# Elecctronic_Dice.net
KiCad netlist of a schematic drawn in EAGLE
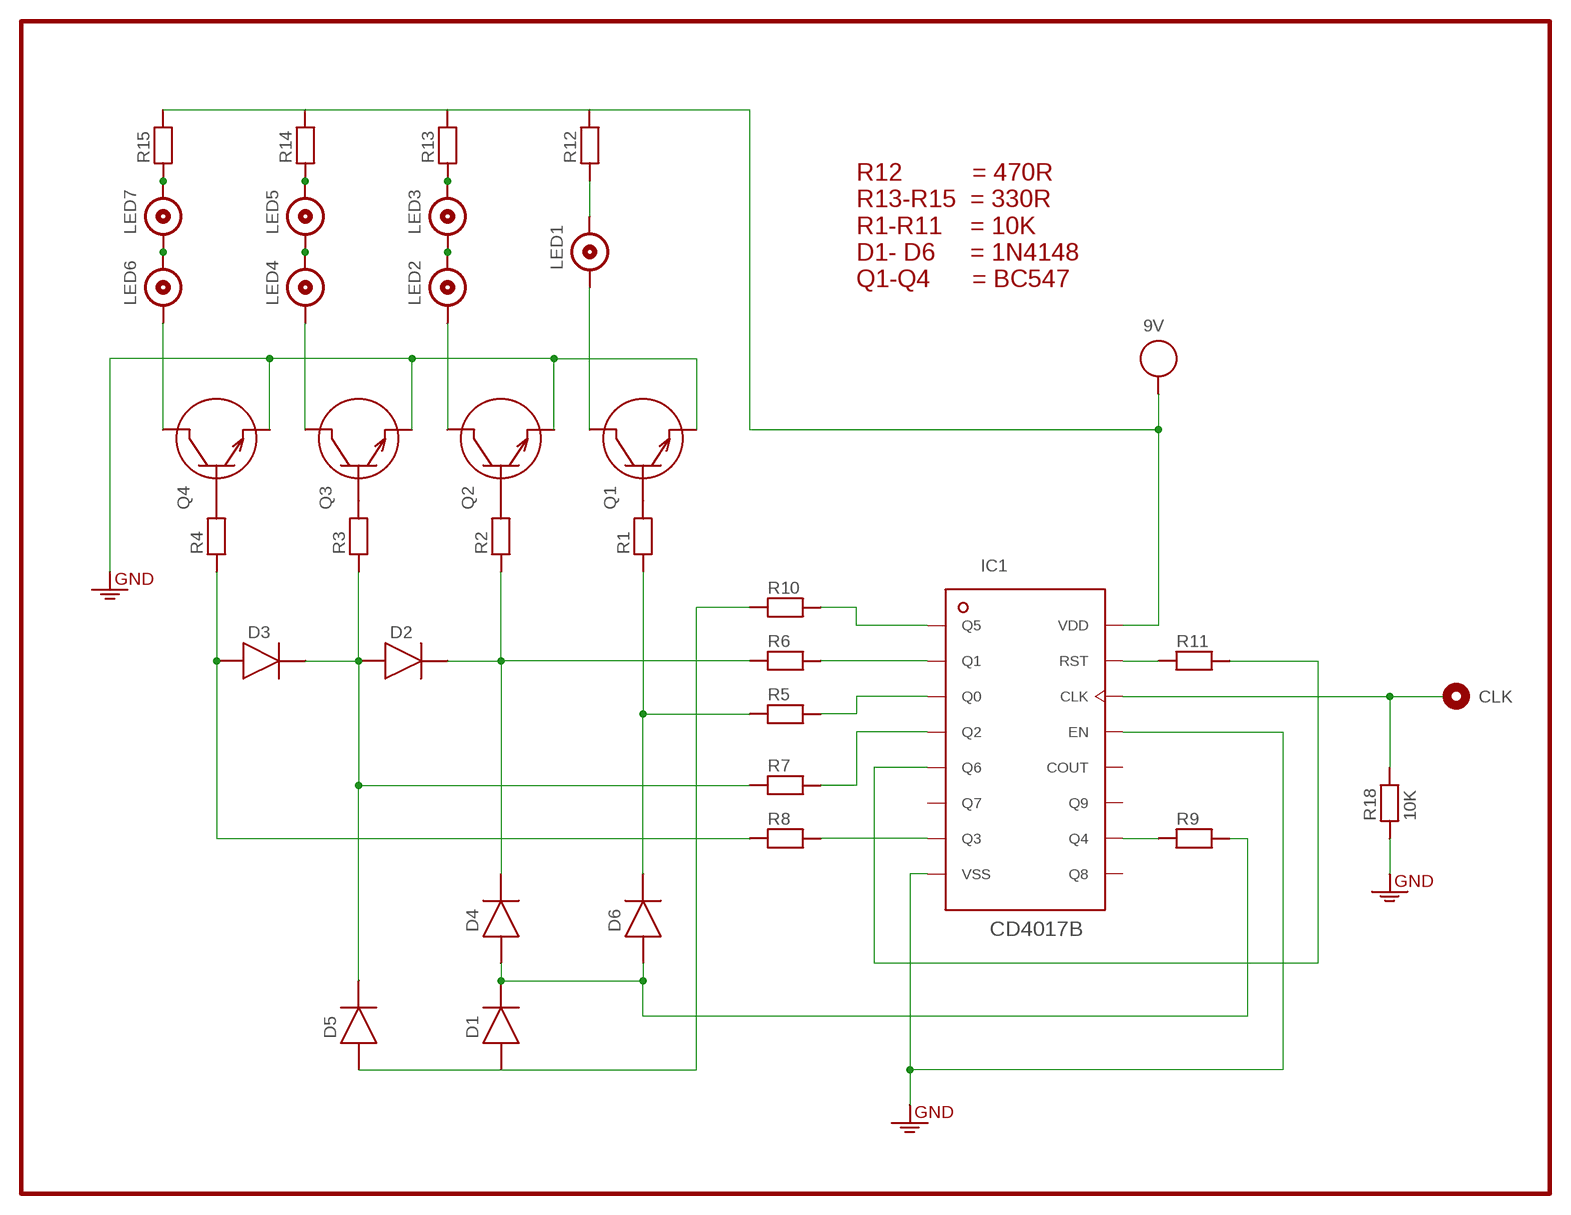
[diagram p0: schematic, sheet 1]
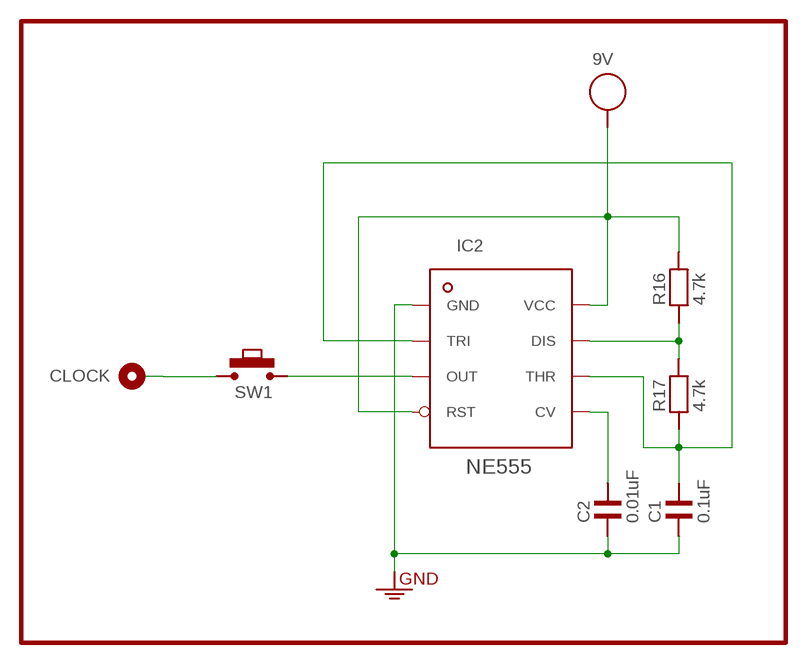
[diagram p1: schematic, sheet 2]

(export (version "E")
  (design (tool "Eeschema 10.0.6"))
  (components
    (comp (ref "CLK")
      (value "POINT")
      (footprint "eagle-import:1POINT")
      (libsource (lib "eagle-import") (part "POINT"))
    )
    (comp (ref "D1")
      (value "DIODE_NORMAL")
      (footprint "eagle-import:DIO_3G")
      (libsource (lib "eagle-import") (part "DIODE_NORMAL"))
    )
    (comp (ref "D2")
      (value "DIODE_NORMAL")
      (footprint "eagle-import:DIO_3G")
      (libsource (lib "eagle-import") (part "DIODE_NORMAL"))
    )
    (comp (ref "D3")
      (value "DIODE_NORMAL")
      (footprint "eagle-import:DIO_3G")
      (libsource (lib "eagle-import") (part "DIODE_NORMAL"))
    )
    (comp (ref "D4")
      (value "DIODE_NORMAL")
      (footprint "eagle-import:DIO_3G")
      (libsource (lib "eagle-import") (part "DIODE_NORMAL"))
    )
    (comp (ref "D5")
      (value "DIODE_NORMAL")
      (footprint "eagle-import:DIO_3G")
      (libsource (lib "eagle-import") (part "DIODE_NORMAL"))
    )
    (comp (ref "D6")
      (value "DIODE_NORMAL")
      (footprint "eagle-import:DIO_3G")
      (libsource (lib "eagle-import") (part "DIODE_NORMAL"))
    )
    (comp (ref "IC1")
      (value "CD4017B")
      (footprint "eagle-import:16PIN_IC")
      (libsource (lib "eagle-import") (part "CD4017B"))
    )
    (comp (ref "LED1")
      (value "LED")
      (footprint "eagle-import:LED_OG")
      (libsource (lib "eagle-import") (part "LED"))
    )
    (comp (ref "LED2")
      (value "LED")
      (footprint "eagle-import:LED_OG")
      (libsource (lib "eagle-import") (part "LED"))
    )
    (comp (ref "LED3")
      (value "LED")
      (footprint "eagle-import:LED_OG")
      (libsource (lib "eagle-import") (part "LED"))
    )
    (comp (ref "LED4")
      (value "LED")
      (footprint "eagle-import:LED_OG")
      (libsource (lib "eagle-import") (part "LED"))
    )
    (comp (ref "LED5")
      (value "LED")
      (footprint "eagle-import:LED_OG")
      (libsource (lib "eagle-import") (part "LED"))
    )
    (comp (ref "LED6")
      (value "LED")
      (footprint "eagle-import:LED_OG")
      (libsource (lib "eagle-import") (part "LED"))
    )
    (comp (ref "LED7")
      (value "LED")
      (footprint "eagle-import:LED_OG")
      (libsource (lib "eagle-import") (part "LED"))
    )
    (comp (ref "Q1")
      (value "TRANSISTOR_NPN")
      (footprint "eagle-import:TRANSISTOR")
      (libsource (lib "eagle-import") (part "TRANSISTOR_NPN"))
    )
    (comp (ref "Q2")
      (value "TRANSISTOR_NPN")
      (footprint "eagle-import:TRANSISTOR")
      (libsource (lib "eagle-import") (part "TRANSISTOR_NPN"))
    )
    (comp (ref "Q3")
      (value "TRANSISTOR_NPN")
      (footprint "eagle-import:TRANSISTOR")
      (libsource (lib "eagle-import") (part "TRANSISTOR_NPN"))
    )
    (comp (ref "Q4")
      (value "TRANSISTOR_NPN")
      (footprint "eagle-import:TRANSISTOR")
      (libsource (lib "eagle-import") (part "TRANSISTOR_NPN"))
    )
    (comp (ref "R1")
      (value "RESISTOR_NORMAL")
      (footprint "eagle-import:RES_3G")
      (libsource (lib "eagle-import") (part "RESISTOR_NORMAL"))
    )
    (comp (ref "R2")
      (value "RESISTOR_NORMAL")
      (footprint "eagle-import:RES_3G")
      (libsource (lib "eagle-import") (part "RESISTOR_NORMAL"))
    )
    (comp (ref "R3")
      (value "RESISTOR_NORMAL")
      (footprint "eagle-import:RES_3G")
      (libsource (lib "eagle-import") (part "RESISTOR_NORMAL"))
    )
    (comp (ref "R4")
      (value "RESISTOR_NORMAL")
      (footprint "eagle-import:RES_3G")
      (libsource (lib "eagle-import") (part "RESISTOR_NORMAL"))
    )
    (comp (ref "R5")
      (value "RESISTOR_NORMAL")
      (footprint "eagle-import:RES_3G")
      (libsource (lib "eagle-import") (part "RESISTOR_NORMAL"))
    )
    (comp (ref "R6")
      (value "RESISTOR_NORMAL")
      (footprint "eagle-import:RES_3G")
      (libsource (lib "eagle-import") (part "RESISTOR_NORMAL"))
    )
    (comp (ref "R7")
      (value "RESISTOR_NORMAL")
      (footprint "eagle-import:RES_3G")
      (libsource (lib "eagle-import") (part "RESISTOR_NORMAL"))
    )
    (comp (ref "R8")
      (value "RESISTOR_NORMAL")
      (footprint "eagle-import:RES_3G")
      (libsource (lib "eagle-import") (part "RESISTOR_NORMAL"))
    )
    (comp (ref "R9")
      (value "RESISTOR_NORMAL")
      (footprint "eagle-import:RES_3G")
      (libsource (lib "eagle-import") (part "RESISTOR_NORMAL"))
    )
    (comp (ref "R10")
      (value "RESISTOR_NORMAL")
      (footprint "eagle-import:RES_3G")
      (libsource (lib "eagle-import") (part "RESISTOR_NORMAL"))
    )
    (comp (ref "R11")
      (value "RESISTOR_NORMAL")
      (footprint "eagle-import:RES_3G")
      (libsource (lib "eagle-import") (part "RESISTOR_NORMAL"))
    )
    (comp (ref "R12")
      (value "RESISTOR_NORMAL")
      (footprint "eagle-import:RES_3G")
      (libsource (lib "eagle-import") (part "RESISTOR_NORMAL"))
    )
    (comp (ref "R13")
      (value "RESISTOR_NORMAL")
      (footprint "eagle-import:RES_3G")
      (libsource (lib "eagle-import") (part "RESISTOR_NORMAL"))
    )
    (comp (ref "R14")
      (value "RESISTOR_NORMAL")
      (footprint "eagle-import:RES_3G")
      (libsource (lib "eagle-import") (part "RESISTOR_NORMAL"))
    )
    (comp (ref "R15")
      (value "RESISTOR_NORMAL")
      (footprint "eagle-import:RES_3G")
      (libsource (lib "eagle-import") (part "RESISTOR_NORMAL"))
    )
    (comp (ref "R18")
      (value "10K")
      (footprint "eagle-import:RES_3G")
      (libsource (lib "eagle-import") (part "RESISTOR_NORMAL"))
    )
    (comp (ref "U$1")
      (value "GND")
      (footprint "eagle-import:1POINT")
      (libsource (lib "eagle-import") (part "SAM Labs Components_GND"))
    )
    (comp (ref "U$2")
      (value "GND")
      (footprint "eagle-import:1POINT")
      (libsource (lib "eagle-import") (part "SAM Labs Components_GND"))
    )
    (comp (ref "U$3")
      (value "9V")
      (footprint "eagle-import:1POINT")
      (libsource (lib "eagle-import") (part "SAM Labs Components_VCC"))
    )
    (comp (ref "U$5")
      (value "GND")
      (footprint "eagle-import:1POINT")
      (libsource (lib "eagle-import") (part "SAM Labs Components_GND"))
    )
    (comp (ref "9V")
      (value "9V")
      (footprint "eagle-import:1POINT")
      (libsource (lib "eagle-import") (part "VCC"))
    )
    (comp (ref "C1")
      (value "0.1uF")
      (footprint "eagle-import:2POINT")
      (libsource (lib "eagle-import") (part "CAP_NPOL"))
    )
    (comp (ref "C2")
      (value "0.01uF")
      (footprint "eagle-import:2POINT")
      (libsource (lib "eagle-import") (part "CAP_NPOL"))
    )
    (comp (ref "CLOCK")
      (value "POINT")
      (footprint "eagle-import:1POINT")
      (libsource (lib "eagle-import") (part "POINT"))
    )
    (comp (ref "IC2")
      (value "NE555")
      (footprint "eagle-import:8PIN_IC")
      (libsource (lib "eagle-import") (part "NE555"))
    )
    (comp (ref "R16")
      (value "4.7k")
      (footprint "eagle-import:RES_3G")
      (libsource (lib "eagle-import") (part "RESISTOR_NORMAL"))
    )
    (comp (ref "R17")
      (value "4.7k")
      (footprint "eagle-import:RES_3G")
      (libsource (lib "eagle-import") (part "RESISTOR_NORMAL"))
    )
    (comp (ref "SW1")
      (value "PUSHSWITCH")
      (footprint "eagle-import:PUSHSWITCH")
      (libsource (lib "eagle-import") (part "PUSHSWITCH"))
    )
    (comp (ref "U$4")
      (value "GND")
      (footprint "eagle-import:1POINT")
      (libsource (lib "eagle-import") (part "GND"))
    )
  )
  (nets
    (net (code "1") (name "Net-(CLOCK-PadP$1)") (class "Default")
      (node (ref "CLOCK") (pin "P$1") (pinfunction "P$1_P$1") (pintype "power_in"))
      (node (ref "SW1") (pin "P$1") (pinfunction "P$1_P$1") (pintype "bidirectional"))
      (node (ref "SW1") (pin "P$2") (pinfunction "P$1_P$2") (pintype "bidirectional"))
    )
    (net (code "2") (name "Net-(IC1-CLK)") (class "Default")
      (node (ref "CLK") (pin "P$1") (pinfunction "P$1_P$1") (pintype "power_in"))
      (node (ref "IC1") (pin "P$14") (pinfunction "CLK_P$14") (pintype "bidirectional"))
      (node (ref "R18") (pin "P$5") (pinfunction "P$2_P$5") (pintype "bidirectional"))
    )
    (net (code "3") (name "Net-(IC1-EN)") (class "Default")
      (node (ref "IC1") (pin "P$13") (pinfunction "EN_P$13") (pintype "bidirectional"))
      (node (ref "IC1") (pin "P$8") (pinfunction "VSS_P$8") (pintype "power_in"))
      (node (ref "U$2") (pin "P$1") (pinfunction "P$1_P$1") (pintype "bidirectional"))
    )
    (net (code "4") (name "Net-(IC1-Q0)") (class "Default")
      (node (ref "IC1") (pin "P$3") (pinfunction "Q0_P$3") (pintype "bidirectional"))
      (node (ref "R5") (pin "P$5") (pinfunction "P$2_P$5") (pintype "bidirectional"))
    )
    (net (code "5") (name "Net-(IC1-Q1)") (class "Default")
      (node (ref "IC1") (pin "P$2") (pinfunction "Q1_P$2") (pintype "bidirectional"))
      (node (ref "R6") (pin "P$5") (pinfunction "P$2_P$5") (pintype "bidirectional"))
    )
    (net (code "6") (name "Net-(IC1-Q2)") (class "Default")
      (node (ref "IC1") (pin "P$4") (pinfunction "Q2_P$4") (pintype "bidirectional"))
      (node (ref "R7") (pin "P$5") (pinfunction "P$2_P$5") (pintype "bidirectional"))
    )
    (net (code "7") (name "Net-(IC1-Q3)") (class "Default")
      (node (ref "IC1") (pin "P$7") (pinfunction "Q3_P$7") (pintype "bidirectional"))
      (node (ref "R8") (pin "P$5") (pinfunction "P$2_P$5") (pintype "bidirectional"))
    )
    (net (code "8") (name "Net-(IC1-Q4)") (class "Default")
      (node (ref "IC1") (pin "P$10") (pinfunction "Q4_P$10") (pintype "bidirectional"))
      (node (ref "R9") (pin "P$3") (pinfunction "P$1_P$3") (pintype "bidirectional"))
    )
    (net (code "9") (name "Net-(IC1-Q5)") (class "Default")
      (node (ref "IC1") (pin "P$1") (pinfunction "Q5_P$1") (pintype "bidirectional"))
      (node (ref "R10") (pin "P$5") (pinfunction "P$2_P$5") (pintype "bidirectional"))
    )
    (net (code "10") (name "Net-(IC1-Q6)") (class "Default")
      (node (ref "IC1") (pin "P$5") (pinfunction "Q6_P$5") (pintype "bidirectional"))
      (node (ref "R11") (pin "P$5") (pinfunction "P$2_P$5") (pintype "bidirectional"))
    )
    (net (code "11") (name "Net-(IC1-RST)") (class "Default")
      (node (ref "IC1") (pin "P$15") (pinfunction "RST_P$15") (pintype "bidirectional"))
      (node (ref "R11") (pin "P$3") (pinfunction "P$1_P$3") (pintype "bidirectional"))
    )
    (net (code "12") (name "Net-(IC1-VDD)") (class "Default")
      (node (ref "IC1") (pin "P$16") (pinfunction "VDD_P$16") (pintype "power_in"))
      (node (ref "R12") (pin "P$5") (pinfunction "P$2_P$5") (pintype "bidirectional"))
      (node (ref "R15") (pin "P$5") (pinfunction "P$2_P$5") (pintype "bidirectional"))
      (node (ref "U$3") (pin "P$1") (pinfunction "P$1_P$1") (pintype "bidirectional"))
    )
    (net (code "13") (name "Net-(IC2-CV)") (class "Default")
      (node (ref "C2") (pin "P$2") (pinfunction "P$2_P$2") (pintype "bidirectional"))
      (node (ref "IC2") (pin "P$5") (pinfunction "CV_P$5") (pintype "bidirectional"))
    )
    (net (code "14") (name "Net-(IC2-DIS)") (class "Default")
      (node (ref "IC2") (pin "P$7") (pinfunction "DIS_P$7") (pintype "bidirectional"))
      (node (ref "R16") (pin "P$3") (pinfunction "P$1_P$3") (pintype "bidirectional"))
      (node (ref "R17") (pin "P$5") (pinfunction "P$2_P$5") (pintype "bidirectional"))
    )
    (net (code "15") (name "Net-(IC2-GND)") (class "Default")
      (node (ref "C1") (pin "P$1") (pinfunction "P$1_P$1") (pintype "bidirectional"))
      (node (ref "C2") (pin "P$1") (pinfunction "P$1_P$1") (pintype "bidirectional"))
      (node (ref "IC2") (pin "P$1") (pinfunction "GND_P$1") (pintype "power_in"))
      (node (ref "U$4") (pin "P$1") (pinfunction "P$1_P$1") (pintype "power_in"))
    )
    (net (code "16") (name "Net-(IC2-OUT)") (class "Default")
      (node (ref "IC2") (pin "P$3") (pinfunction "OUT_P$3") (pintype "bidirectional"))
      (node (ref "SW1") (pin "P$3") (pinfunction "P$2_P$3") (pintype "bidirectional"))
      (node (ref "SW1") (pin "P$4") (pinfunction "P$2_P$4") (pintype "bidirectional"))
    )
    (net (code "17") (name "Net-(IC2-RST)") (class "Default")
      (node (ref "9V") (pin "P$1") (pinfunction "P$1_P$1") (pintype "power_in"))
      (node (ref "IC2") (pin "P$4") (pinfunction "RST_P$4") (pintype "bidirectional"))
      (node (ref "IC2") (pin "P$8") (pinfunction "VCC_P$8") (pintype "power_in"))
      (node (ref "R16") (pin "P$5") (pinfunction "P$2_P$5") (pintype "bidirectional"))
    )
    (net (code "18") (name "Net-(IC2-THR)") (class "Default")
      (node (ref "C1") (pin "P$2") (pinfunction "P$2_P$2") (pintype "bidirectional"))
      (node (ref "IC2") (pin "P$2") (pinfunction "TRI_P$2") (pintype "bidirectional"))
      (node (ref "IC2") (pin "P$6") (pinfunction "THR_P$6") (pintype "bidirectional"))
      (node (ref "R17") (pin "P$3") (pinfunction "P$1_P$3") (pintype "bidirectional"))
    )
    (net (code "19") (name "Net-(LED1-PadP$2)") (class "Default")
      (node (ref "LED1") (pin "P$2") (pinfunction "P$2_P$2") (pintype "bidirectional"))
      (node (ref "Q1") (pin "P$3") (pinfunction "P$3_P$3") (pintype "bidirectional"))
    )
    (net (code "20") (name "Net-(LED2-PadP$1)") (class "Default")
      (node (ref "LED2") (pin "P$1") (pinfunction "P$1_P$1") (pintype "bidirectional"))
      (node (ref "LED3") (pin "P$2") (pinfunction "P$2_P$2") (pintype "bidirectional"))
    )
    (net (code "21") (name "Net-(LED2-PadP$2)") (class "Default")
      (node (ref "LED2") (pin "P$2") (pinfunction "P$2_P$2") (pintype "bidirectional"))
      (node (ref "Q2") (pin "P$3") (pinfunction "P$3_P$3") (pintype "bidirectional"))
    )
    (net (code "22") (name "Net-(LED4-PadP$1)") (class "Default")
      (node (ref "LED4") (pin "P$1") (pinfunction "P$1_P$1") (pintype "bidirectional"))
      (node (ref "LED5") (pin "P$2") (pinfunction "P$2_P$2") (pintype "bidirectional"))
    )
    (net (code "23") (name "Net-(LED4-PadP$2)") (class "Default")
      (node (ref "LED4") (pin "P$2") (pinfunction "P$2_P$2") (pintype "bidirectional"))
      (node (ref "Q3") (pin "P$3") (pinfunction "P$3_P$3") (pintype "bidirectional"))
    )
    (net (code "24") (name "Net-(LED6-PadP$1)") (class "Default")
      (node (ref "LED6") (pin "P$1") (pinfunction "P$1_P$1") (pintype "bidirectional"))
      (node (ref "LED7") (pin "P$2") (pinfunction "P$2_P$2") (pintype "bidirectional"))
    )
    (net (code "25") (name "Net-(LED6-PadP$2)") (class "Default")
      (node (ref "LED6") (pin "P$2") (pinfunction "P$2_P$2") (pintype "bidirectional"))
      (node (ref "Q4") (pin "P$3") (pinfunction "P$3_P$3") (pintype "bidirectional"))
    )
    (net (code "26") (name "Net-(Q1-PadP$1)") (class "Default")
      (node (ref "Q1") (pin "P$1") (pinfunction "P$1_P$1") (pintype "bidirectional"))
      (node (ref "Q2") (pin "P$1") (pinfunction "P$1_P$1") (pintype "bidirectional"))
      (node (ref "Q3") (pin "P$1") (pinfunction "P$1_P$1") (pintype "bidirectional"))
      (node (ref "Q4") (pin "P$1") (pinfunction "P$1_P$1") (pintype "bidirectional"))
      (node (ref "U$1") (pin "P$1") (pinfunction "P$1_P$1") (pintype "bidirectional"))
    )
    (net (code "27") (name "Net-(R1-P$1)") (class "Default")
      (node (ref "D6") (pin "N") (pinfunction "N_N") (pintype "bidirectional"))
      (node (ref "R1") (pin "P$3") (pinfunction "P$1_P$3") (pintype "bidirectional"))
      (node (ref "R5") (pin "P$3") (pinfunction "P$1_P$3") (pintype "bidirectional"))
    )
    (net (code "28") (name "Net-(R1-P$2)") (class "Default")
      (node (ref "Q1") (pin "P$2") (pinfunction "P$2_P$2") (pintype "bidirectional"))
      (node (ref "R1") (pin "P$5") (pinfunction "P$2_P$5") (pintype "bidirectional"))
    )
    (net (code "29") (name "Net-(R2-P$1)") (class "Default")
      (node (ref "D2") (pin "N") (pinfunction "N_N") (pintype "bidirectional"))
      (node (ref "D4") (pin "N") (pinfunction "N_N") (pintype "bidirectional"))
      (node (ref "R2") (pin "P$3") (pinfunction "P$1_P$3") (pintype "bidirectional"))
      (node (ref "R6") (pin "P$3") (pinfunction "P$1_P$3") (pintype "bidirectional"))
    )
    (net (code "30") (name "Net-(R2-P$2)") (class "Default")
      (node (ref "Q2") (pin "P$2") (pinfunction "P$2_P$2") (pintype "bidirectional"))
      (node (ref "R2") (pin "P$5") (pinfunction "P$2_P$5") (pintype "bidirectional"))
    )
    (net (code "31") (name "Net-(R3-P$1)") (class "Default")
      (node (ref "D2") (pin "P") (pinfunction "P_P") (pintype "bidirectional"))
      (node (ref "D3") (pin "N") (pinfunction "N_N") (pintype "bidirectional"))
      (node (ref "D5") (pin "N") (pinfunction "N_N") (pintype "bidirectional"))
      (node (ref "R3") (pin "P$3") (pinfunction "P$1_P$3") (pintype "bidirectional"))
      (node (ref "R7") (pin "P$3") (pinfunction "P$1_P$3") (pintype "bidirectional"))
    )
    (net (code "32") (name "Net-(R3-P$2)") (class "Default")
      (node (ref "Q3") (pin "P$2") (pinfunction "P$2_P$2") (pintype "bidirectional"))
      (node (ref "R3") (pin "P$5") (pinfunction "P$2_P$5") (pintype "bidirectional"))
    )
    (net (code "33") (name "Net-(R4-P$1)") (class "Default")
      (node (ref "D3") (pin "P") (pinfunction "P_P") (pintype "bidirectional"))
      (node (ref "R4") (pin "P$3") (pinfunction "P$1_P$3") (pintype "bidirectional"))
      (node (ref "R8") (pin "P$3") (pinfunction "P$1_P$3") (pintype "bidirectional"))
    )
    (net (code "34") (name "Net-(R4-P$2)") (class "Default")
      (node (ref "Q4") (pin "P$2") (pinfunction "P$2_P$2") (pintype "bidirectional"))
      (node (ref "R4") (pin "P$5") (pinfunction "P$2_P$5") (pintype "bidirectional"))
    )
    (net (code "35") (name "Net-(R9-P$2)") (class "Default")
      (node (ref "D1") (pin "N") (pinfunction "N_N") (pintype "bidirectional"))
      (node (ref "D4") (pin "P") (pinfunction "P_P") (pintype "bidirectional"))
      (node (ref "D6") (pin "P") (pinfunction "P_P") (pintype "bidirectional"))
      (node (ref "R9") (pin "P$5") (pinfunction "P$2_P$5") (pintype "bidirectional"))
    )
    (net (code "36") (name "Net-(R10-P$1)") (class "Default")
      (node (ref "D1") (pin "P") (pinfunction "P_P") (pintype "bidirectional"))
      (node (ref "D5") (pin "P") (pinfunction "P_P") (pintype "bidirectional"))
      (node (ref "R10") (pin "P$3") (pinfunction "P$1_P$3") (pintype "bidirectional"))
    )
    (net (code "37") (name "Net-(R12-P$1)") (class "Default")
      (node (ref "LED1") (pin "P$1") (pinfunction "P$1_P$1") (pintype "bidirectional"))
      (node (ref "R12") (pin "P$3") (pinfunction "P$1_P$3") (pintype "bidirectional"))
    )
    (net (code "38") (name "Net-(R13-P$1)") (class "Default")
      (node (ref "LED3") (pin "P$1") (pinfunction "P$1_P$1") (pintype "bidirectional"))
      (node (ref "R13") (pin "P$3") (pinfunction "P$1_P$3") (pintype "bidirectional"))
    )
    (net (code "39") (name "Net-(R14-P$1)") (class "Default")
      (node (ref "LED5") (pin "P$1") (pinfunction "P$1_P$1") (pintype "bidirectional"))
      (node (ref "R14") (pin "P$3") (pinfunction "P$1_P$3") (pintype "bidirectional"))
    )
    (net (code "40") (name "Net-(R15-P$1)") (class "Default")
      (node (ref "LED7") (pin "P$1") (pinfunction "P$1_P$1") (pintype "bidirectional"))
      (node (ref "R15") (pin "P$3") (pinfunction "P$1_P$3") (pintype "bidirectional"))
    )
    (net (code "41") (name "Net-(R18-P$1)") (class "Default")
      (node (ref "R18") (pin "P$3") (pinfunction "P$1_P$3") (pintype "bidirectional"))
      (node (ref "U$5") (pin "P$1") (pinfunction "P$1_P$1") (pintype "bidirectional"))
    )
    (net (code "42") (name "unconnected-(IC1-COUT-PadP$12)") (class "Default")
      (node (ref "IC1") (pin "P$12") (pinfunction "COUT_P$12") (pintype "bidirectional"))
    )
    (net (code "43") (name "unconnected-(IC1-Q7-PadP$6)") (class "Default")
      (node (ref "IC1") (pin "P$6") (pinfunction "Q7_P$6") (pintype "bidirectional"))
    )
    (net (code "44") (name "unconnected-(IC1-Q8-PadP$9)") (class "Default")
      (node (ref "IC1") (pin "P$9") (pinfunction "Q8_P$9") (pintype "bidirectional"))
    )
    (net (code "45") (name "unconnected-(IC1-Q9-PadP$11)") (class "Default")
      (node (ref "IC1") (pin "P$11") (pinfunction "Q9_P$11") (pintype "bidirectional"))
    )
    (net (code "46") (name "unconnected-(R13-P$2-PadP$5)") (class "Default")
      (node (ref "R13") (pin "P$5") (pinfunction "P$2_P$5") (pintype "bidirectional"))
    )
    (net (code "47") (name "unconnected-(R14-P$2-PadP$5)") (class "Default")
      (node (ref "R14") (pin "P$5") (pinfunction "P$2_P$5") (pintype "bidirectional"))
    )
  )
)
